# ISO_Power.net
KiCad netlist of a schematic drawn in Altium Designer
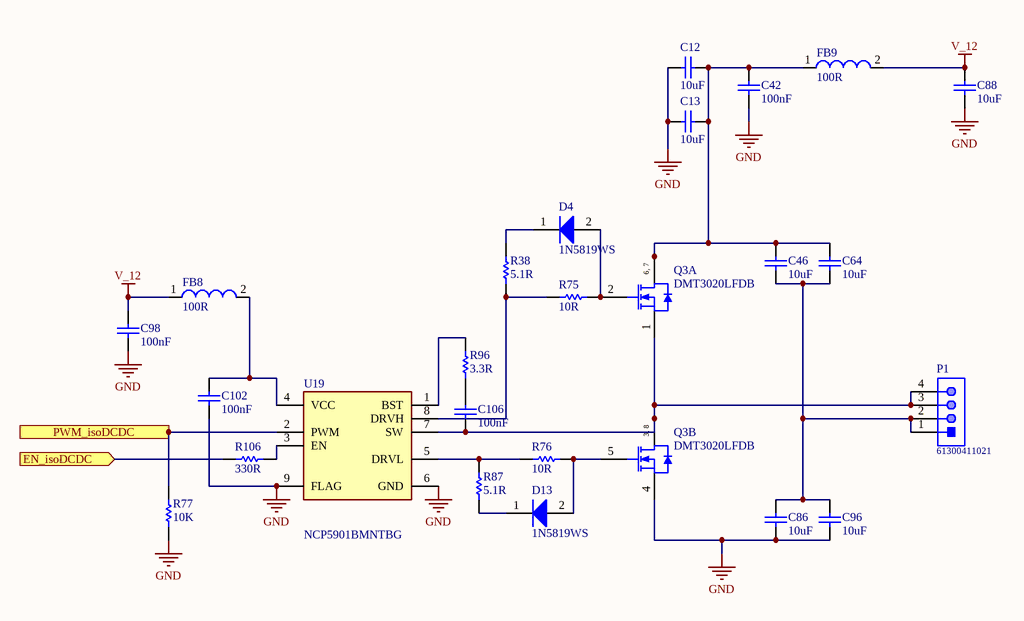
[diagram p0: ISO_Power.SchDoc]

(export (version "E")
  (design (tool "Eeschema 10.0.6"))
  (components
    (comp (ref "C12")
      (value "10uF")
      (footprint "CAPC2013X140X45NL15T25")
      (description "X5R 25V ±10% 10uF 0805 Multilayer Ceramic Capacitors MLCC - SMD/SMT ROHS")
      (fields (field (name "PART NUMBER") "GRM21BR71A106KE51L") (field (name "MANUFACTURER") "Murata"))
      (libsource (lib "DCDC") (part "CMP-2007-03395-1"))
    )
    (comp (ref "C13")
      (value "10uF")
      (footprint "CAPC2013X140X45NL15T25")
      (description "X5R 25V ±10% 10uF 0805 Multilayer Ceramic Capacitors MLCC - SMD/SMT ROHS")
      (fields (field (name "PART NUMBER") "GRM21BR71A106KE51L") (field (name "MANUFACTURER") "Murata"))
      (libsource (lib "DCDC") (part "CMP-2007-03395-1"))
    )
    (comp (ref "C42")
      (value "100nF")
      (footprint "CAPC1608X90X35NL10T15")
      (description "X7R 100nF ±10% 50V 0603 Multilayer Ceramic Capacitors MLCC - SMD/SMT ROHS")
      (fields (field (name "PART NUMBER") "GCM188R72A104KA64D") (field (name "MANUFACTURER") "Murata"))
      (libsource (lib "DCDC") (part "CAP"))
    )
    (comp (ref "C46")
      (value "10uF")
      (footprint "CAPC2013X140X45NL15T25")
      (description "X5R 25V ±10% 10uF 0805 Multilayer Ceramic Capacitors MLCC - SMD/SMT ROHS")
      (fields (field (name "PART NUMBER") "GRM21BR71A106KE51L") (field (name "MANUFACTURER") "Murata"))
      (libsource (lib "DCDC") (part "CMP-2007-03395-1"))
    )
    (comp (ref "C64")
      (value "10uF")
      (footprint "CAPC2013X140X45NL15T25")
      (description "X5R 25V ±10% 10uF 0805 Multilayer Ceramic Capacitors MLCC - SMD/SMT ROHS")
      (fields (field (name "PART NUMBER") "GRM21BR71A106KE51L") (field (name "MANUFACTURER") "Murata"))
      (libsource (lib "DCDC") (part "CMP-2007-03395-1"))
    )
    (comp (ref "C86")
      (value "10uF")
      (footprint "CAPC2013X140X45NL15T25")
      (description "X5R 25V ±10% 10uF 0805 Multilayer Ceramic Capacitors MLCC - SMD/SMT ROHS")
      (fields (field (name "PART NUMBER") "GRM21BR71A106KE51L") (field (name "MANUFACTURER") "Murata"))
      (libsource (lib "DCDC") (part "CMP-2007-03395-1"))
    )
    (comp (ref "C88")
      (value "10uF")
      (footprint "CAPC2013X140X45NL15T25")
      (description "X5R 25V ±10% 10uF 0805 Multilayer Ceramic Capacitors MLCC - SMD/SMT ROHS")
      (fields (field (name "PART NUMBER") "GRM21BR71A106KE51L") (field (name "MANUFACTURER") "Murata"))
      (libsource (lib "DCDC") (part "CMP-2007-03395-1"))
    )
    (comp (ref "C96")
      (value "10uF")
      (footprint "CAPC2013X140X45NL15T25")
      (description "X5R 25V ±10% 10uF 0805 Multilayer Ceramic Capacitors MLCC - SMD/SMT ROHS")
      (fields (field (name "PART NUMBER") "GRM21BR71A106KE51L") (field (name "MANUFACTURER") "Murata"))
      (libsource (lib "DCDC") (part "CMP-2007-03395-1"))
    )
    (comp (ref "C98")
      (value "100nF")
      (footprint "CAPC1608X90X35NL10T15")
      (description "X7R 100nF ±10% 50V 0603 Multilayer Ceramic Capacitors MLCC - SMD/SMT ROHS")
      (fields (field (name "PART NUMBER") "GCM188R72A104KA64D") (field (name "MANUFACTURER") "Murata"))
      (libsource (lib "DCDC") (part "CAP"))
    )
    (comp (ref "C102")
      (value "100nF")
      (footprint "CAPC1608X90X35NL10T15")
      (description "X7R 100nF ±10% 50V 0603 Multilayer Ceramic Capacitors MLCC - SMD/SMT ROHS")
      (fields (field (name "PART NUMBER") "GCM188R72A104KA64D") (field (name "MANUFACTURER") "Murata"))
      (libsource (lib "DCDC") (part "CAP"))
    )
    (comp (ref "C106")
      (value "100nF")
      (footprint "CAPC1608X90X35NL10T15")
      (description "X7R 100nF ±10% 50V 0603 Multilayer Ceramic Capacitors MLCC - SMD/SMT ROHS")
      (fields (field (name "PART NUMBER") "GCM188R72A104KA64D") (field (name "MANUFACTURER") "Murata"))
      (libsource (lib "DCDC") (part "CAP"))
    )
    (comp (ref "D4")
      (value "1N5819WS")
      (footprint "ONSC-SOD-323-2-477-02_V")
      (description "40V 1A 600mV @ 1A SOD-323 Schottky Barrier Diodes (SBD) ROHS")
      (fields (field (name "PARTNUMBER") "BAT54HT1G") (field (name "MANUFACTURER") "On Semiconductor"))
      (libsource (lib "Altium Content Vault") (part "ONSC-D-K1A2-2"))
    )
    (comp (ref "D13")
      (value "1N5819WS")
      (footprint "ONSC-SOD-323-2-477-02_V")
      (description "40V 1A 600mV @ 1A SOD-323 Schottky Barrier Diodes (SBD) ROHS")
      (fields (field (name "PARTNUMBER") "BAT54HT1G") (field (name "MANUFACTURER") "On Semiconductor"))
      (libsource (lib "Altium Content Vault") (part "ONSC-D-K1A2-2"))
    )
    (comp (ref "FB8")
      (value "100R")
      (footprint "SMD-0603")
      (description "SMD EMI Suppression Ferrite Bead WE-CBF, Z = 1500 Ohm")
      (libsource (lib "Altium Content Vault") (part "PAS-IND-INDUCTOR-2"))
    )
    (comp (ref "FB9")
      (value "100R")
      (footprint "SMD-0603")
      (description "SMD EMI Suppression Ferrite Bead WE-CBF, Z = 1500 Ohm")
      (libsource (lib "DCDC") (part "PAS-IND-INDUCTOR-2"))
    )
    (comp (ref "P1")
      (value "61300411021")
      (footprint "61300411021")
      (description "THT Angled Pin Header WR-PHD, Pitch 2.54 mm, Single Row, 4 pins")
      (fields (field (name "MANUFACTURER") "Wurth Elektronik") (field (name "PUBLISHER") "WurthElektronik"))
      (libsource (lib "DCDC") (part "WE-CN-1P-M-R4"))
    )
    (comp (ref "Q3")
      (value "DMT3020LFDB")
      (footprint "NXP-SOT1118_L")
      (description "Dual N-Channel Trench MOSFET, 30 V, -55 to 150 degC, 8-Pin SOT1118, Reel")
      (fields (field (name "MANUFACTURER") "NXP Semiconductors") (field (name "PARTNUMBER") "PMDPB56XN,115"))
      (libsource (lib "Altium Content Vault") (part "NXP-NNMOS-SGDSGDDD-8_A"))
    )
    (comp (ref "R38")
      (value "5.1R")
      (footprint "RESC1608X55X30NL15T15")
      (description "±1% ±400ppm/℃ 5.1Ω 0.1W 0603 Chip Resistor - Surface Mount ROHS")
      (fields (field (name "PART NUMBER") "ERJ3EKF1803V") (field (name "MANUFACTURER") "Panasonic"))
      (libsource (lib "DCDC") (part "RES"))
    )
    (comp (ref "R75")
      (value "10R")
      (footprint "RESC1608X55X25NL10T15")
      (description "±1% ±400ppm/℃ 10Ω 0.1W 0603 Chip Resistor - Surface Mount ROHS")
      (fields
        (field (name "MANUFACTURER") "Yageo")
        (field (name "MANUFACTURER PART NUMBER") "RC0603FR-0710RL")
      )
      (libsource (lib "Altium Content Vault") (part "RES-2"))
    )
    (comp (ref "R76")
      (value "10R")
      (footprint "RESC1608X55X25NL10T15")
      (description "±1% ±400ppm/℃ 10Ω 0.1W 0603 Chip Resistor - Surface Mount ROHS")
      (fields
        (field (name "MANUFACTURER") "Yageo")
        (field (name "MANUFACTURER PART NUMBER") "RC0603FR-0710RL")
      )
      (libsource (lib "Altium Content Vault") (part "RES-2"))
    )
    (comp (ref "R77")
      (value "10K")
      (footprint "RESC1608X55X25NL10T15")
      (description "±1% ±100ppm/℃ 10kΩ 0.1W 0603 Chip Resistor - Surface Mount ROHS")
      (fields
        (field (name "MANUFACTURER") "Yageo")
        (field (name "MANUFACTURER PART NUMBER") "RC0603JR-071ML")
      )
      (libsource (lib "DCDC") (part "RES-2"))
    )
    (comp (ref "R87")
      (value "5.1R")
      (footprint "RESC1608X55X30NL15T15")
      (description "±1% ±400ppm/℃ 5.1Ω 0.1W 0603 Chip Resistor - Surface Mount ROHS")
      (fields (field (name "PART NUMBER") "ERJ3EKF1803V") (field (name "MANUFACTURER") "Panasonic"))
      (libsource (lib "DCDC") (part "RES"))
    )
    (comp (ref "R96")
      (value "3.3R")
      (footprint "RESC1608X55X30NL15T15")
      (description "RES SMD 3.3 OHM 1% 1/10W 0603")
      (fields (field (name "PART NUMBER") "ERJ-3RQF3R3V") (field (name "MANUFACTURER") "Panasonic"))
      (libsource (lib "Altium Content Vault") (part "RES"))
    )
    (comp (ref "R106")
      (value "330R")
      (footprint "RESC1608X55X25NL10T15")
      (description "±1% 330Ω ±100ppm/℃ 0.1W 0603 Chip Resistor - Surface Mount ROHS")
      (fields (field (name "TOLERANCE") "10%") (field (name "MANUFACTURER") "Yageo"))
      (libsource (lib "DCDC") (part "RES-2"))
    )
    (comp (ref "U19")
      (value "NCP5901BMNTBG")
      (footprint "SamacSys:SON50P200X200X100-9N")
      (description "Integrated Circuit")
      (fields (field (name "MOUSER PART NUMBER") "863-NCP5901BMNTBG"))
      (libsource (lib "*") (part "NCP5901BMNTBG"))
    )
  )
  (nets
    (net (code "1") (name "/EN_isoDCDC") (class "Default")
      (node (ref "R106") (pin "2") (pinfunction "2_2") (pintype "passive"))
    )
    (net (code "2") (name "/PWM_isoDCDC") (class "Default")
      (node (ref "R77") (pin "2") (pinfunction "2_2") (pintype "passive"))
      (node (ref "U19") (pin "2") (pinfunction "PWM_2") (pintype "passive"))
    )
    (net (code "3") (name "GND") (class "Default")
      (node (ref "C102") (pin "1") (pinfunction "1_1") (pintype "passive"))
      (node (ref "C12") (pin "2") (pinfunction "2_2") (pintype "passive"))
      (node (ref "C13") (pin "2") (pinfunction "2_2") (pintype "passive"))
      (node (ref "C42") (pin "1") (pinfunction "1_1") (pintype "passive"))
      (node (ref "C86") (pin "2") (pinfunction "2_2") (pintype "passive"))
      (node (ref "C88") (pin "2") (pinfunction "2_2") (pintype "passive"))
      (node (ref "C96") (pin "2") (pinfunction "2_2") (pintype "passive"))
      (node (ref "C98") (pin "1") (pinfunction "1_1") (pintype "passive"))
      (node (ref "Q3") (pin "4") (pinfunction "S2_4") (pintype "passive"))
      (node (ref "R77") (pin "1") (pinfunction "1_1") (pintype "passive"))
      (node (ref "U19") (pin "6") (pinfunction "GND_6") (pintype "passive"))
      (node (ref "U19") (pin "9") (pinfunction "FLAG_9") (pintype "passive"))
    )
    (net (code "4") (name "Net-(C12-Pad1)") (class "Default")
      (node (ref "C12") (pin "1") (pinfunction "1_1") (pintype "passive"))
      (node (ref "C13") (pin "1") (pinfunction "1_1") (pintype "passive"))
      (node (ref "C42") (pin "2") (pinfunction "2_2") (pintype "passive"))
      (node (ref "C46") (pin "1") (pinfunction "1_1") (pintype "passive"))
      (node (ref "C64") (pin "1") (pinfunction "1_1") (pintype "passive"))
      (node (ref "FB9") (pin "1") (pinfunction "1_1") (pintype "passive"))
      (node (ref "Q3") (pin "6") (pinfunction "D1_6") (pintype "passive"))
      (node (ref "Q3") (pin "7") (pinfunction "D1_7") (pintype "passive"))
    )
    (net (code "5") (name "Net-(C46-Pad2)") (class "Default")
      (node (ref "C46") (pin "2") (pinfunction "2_2") (pintype "passive"))
      (node (ref "C64") (pin "2") (pinfunction "2_2") (pintype "passive"))
      (node (ref "C86") (pin "1") (pinfunction "1_1") (pintype "passive"))
      (node (ref "C96") (pin "1") (pinfunction "1_1") (pintype "passive"))
      (node (ref "P1") (pin "1") (pinfunction "1_1") (pintype "passive"))
      (node (ref "P1") (pin "2") (pinfunction "2_2") (pintype "passive"))
    )
    (net (code "6") (name "Net-(C106-Pad2)") (class "Default")
      (node (ref "C106") (pin "2") (pinfunction "2_2") (pintype "passive"))
      (node (ref "R96") (pin "1") (pinfunction "1_1") (pintype "passive"))
    )
    (net (code "7") (name "Net-(D4-A)") (class "Default")
      (node (ref "D4") (pin "2") (pinfunction "A_2") (pintype "passive"))
      (node (ref "Q3") (pin "2") (pinfunction "G1_2") (pintype "passive"))
      (node (ref "R75") (pin "2") (pinfunction "2_2") (pintype "passive"))
    )
    (net (code "8") (name "Net-(D4-K)") (class "Default")
      (node (ref "D4") (pin "1") (pinfunction "K_1") (pintype "passive"))
      (node (ref "R38") (pin "2") (pinfunction "2_2") (pintype "passive"))
    )
    (net (code "9") (name "Net-(D13-A)") (class "Default")
      (node (ref "D13") (pin "2") (pinfunction "A_2") (pintype "passive"))
      (node (ref "Q3") (pin "5") (pinfunction "G2_5") (pintype "passive"))
      (node (ref "R76") (pin "2") (pinfunction "2_2") (pintype "passive"))
    )
    (net (code "10") (name "Net-(D13-K)") (class "Default")
      (node (ref "D13") (pin "1") (pinfunction "K_1") (pintype "passive"))
      (node (ref "R87") (pin "1") (pinfunction "1_1") (pintype "passive"))
    )
    (net (code "11") (name "Net-(Q3A-S1)") (class "Default")
      (node (ref "C106") (pin "1") (pinfunction "1_1") (pintype "passive"))
      (node (ref "P1") (pin "3") (pinfunction "3_3") (pintype "passive"))
      (node (ref "P1") (pin "4") (pinfunction "4_4") (pintype "passive"))
      (node (ref "Q3") (pin "1") (pinfunction "S1_1") (pintype "passive"))
      (node (ref "Q3") (pin "3") (pinfunction "D2_3") (pintype "passive"))
      (node (ref "Q3") (pin "8") (pinfunction "D2_8") (pintype "passive"))
      (node (ref "U19") (pin "7") (pinfunction "SW_7") (pintype "passive"))
    )
    (net (code "12") (name "Net-(U19-BST)") (class "Default")
      (node (ref "R96") (pin "2") (pinfunction "2_2") (pintype "passive"))
      (node (ref "U19") (pin "1") (pinfunction "BST_1") (pintype "passive"))
    )
    (net (code "13") (name "Net-(U19-DRVH)") (class "Default")
      (node (ref "R38") (pin "1") (pinfunction "1_1") (pintype "passive"))
      (node (ref "R75") (pin "1") (pinfunction "1_1") (pintype "passive"))
      (node (ref "U19") (pin "8") (pinfunction "DRVH_8") (pintype "passive"))
    )
    (net (code "14") (name "Net-(U19-DRVL)") (class "Default")
      (node (ref "R76") (pin "1") (pinfunction "1_1") (pintype "passive"))
      (node (ref "R87") (pin "2") (pinfunction "2_2") (pintype "passive"))
      (node (ref "U19") (pin "5") (pinfunction "DRVL_5") (pintype "passive"))
    )
    (net (code "15") (name "Net-(U19-EN)") (class "Default")
      (node (ref "R106") (pin "1") (pinfunction "1_1") (pintype "passive"))
      (node (ref "U19") (pin "3") (pinfunction "EN_3") (pintype "passive"))
    )
    (net (code "16") (name "Net-(U19-VCC)") (class "Default")
      (node (ref "C102") (pin "2") (pinfunction "2_2") (pintype "passive"))
      (node (ref "FB8") (pin "2") (pinfunction "2_2") (pintype "passive"))
      (node (ref "U19") (pin "4") (pinfunction "VCC_4") (pintype "passive"))
    )
    (net (code "17") (name "V_12") (class "Default")
      (node (ref "C88") (pin "1") (pinfunction "1_1") (pintype "passive"))
      (node (ref "C98") (pin "2") (pinfunction "2_2") (pintype "passive"))
      (node (ref "FB8") (pin "1") (pinfunction "1_1") (pintype "passive"))
      (node (ref "FB9") (pin "2") (pinfunction "2_2") (pintype "passive"))
    )
  )
)
